# RedFly-Shield_v12.net
KiCad netlist of a schematic drawn in EAGLE
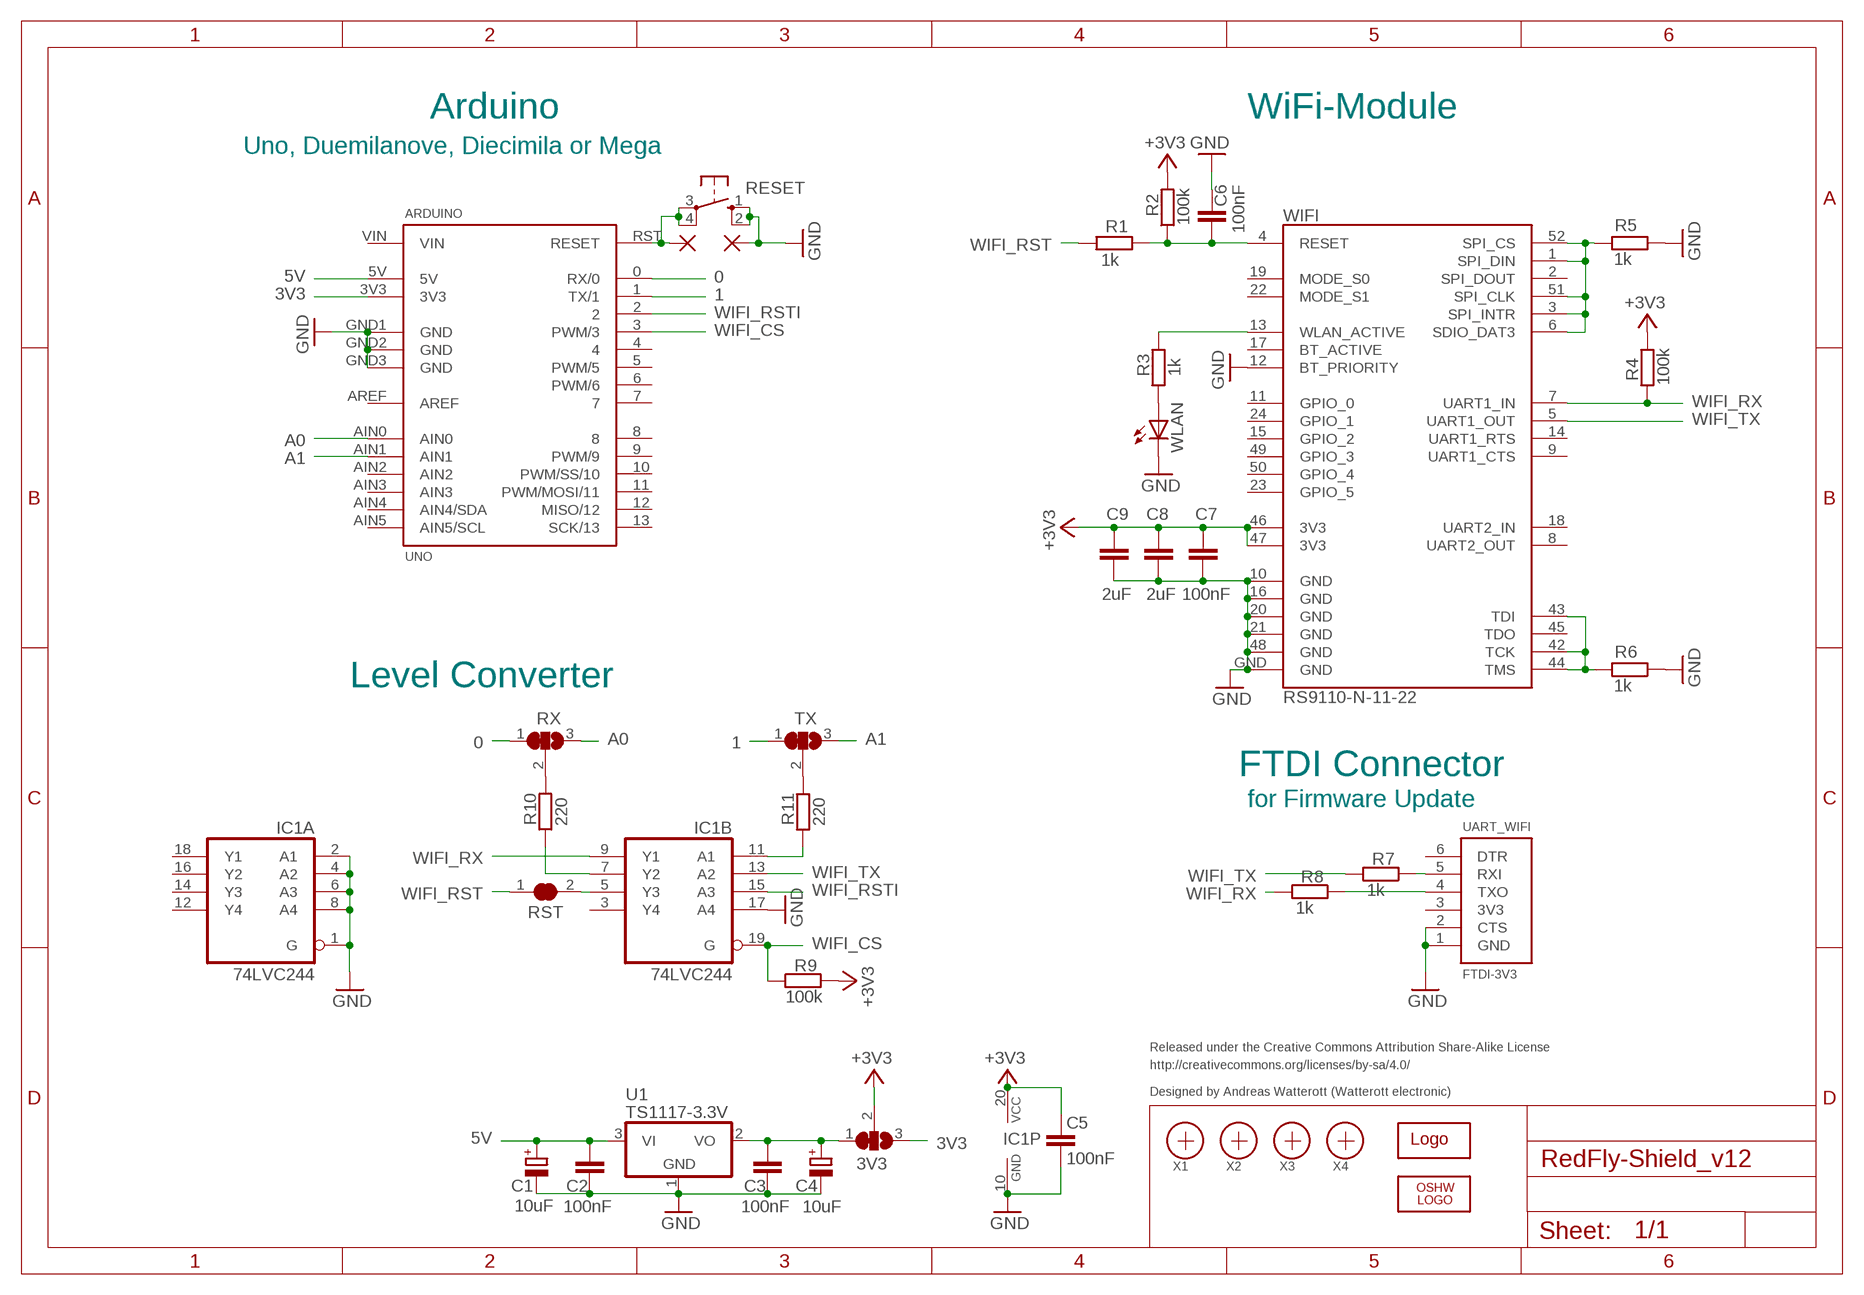
[diagram p0: schematic, sheet 1]

(export (version "E")
  (design (tool "Eeschema 10.0.6"))
  (components
    (comp (ref "3V3")
      (value "SJ2W")
      (footprint "eagle-import:SJ_2")
      (libsource (lib "eagle-import") (part "SJ2W"))
    )
    (comp (ref "ARDUINO")
      (value "UNO")
      (footprint "eagle-import:DUEMILANOVE")
      (libsource (lib "eagle-import") (part "DUEMILANOVE"))
    )
    (comp (ref "C1")
      (value "10uF")
      (footprint "eagle-import:153CLV-0505")
      (libsource (lib "eagle-import") (part "CPOL-EU153CLV-0505"))
    )
    (comp (ref "C2")
      (value "100nF")
      (footprint "eagle-import:C0603")
      (libsource (lib "eagle-import") (part "C-EUC0603"))
    )
    (comp (ref "C3")
      (value "100nF")
      (footprint "eagle-import:C0603")
      (libsource (lib "eagle-import") (part "C-EUC0603"))
    )
    (comp (ref "C4")
      (value "10uF")
      (footprint "eagle-import:153CLV-0505")
      (libsource (lib "eagle-import") (part "CPOL-EU153CLV-0505"))
    )
    (comp (ref "C5")
      (value "100nF")
      (footprint "eagle-import:C0603")
      (libsource (lib "eagle-import") (part "C-EUC0603"))
    )
    (comp (ref "C6")
      (value "100nF")
      (footprint "eagle-import:C0603")
      (libsource (lib "eagle-import") (part "C-EUC0603"))
    )
    (comp (ref "C7")
      (value "100nF")
      (footprint "eagle-import:C0603")
      (libsource (lib "eagle-import") (part "C-EUC0603"))
    )
    (comp (ref "C8")
      (value "2uF")
      (footprint "eagle-import:C0603")
      (libsource (lib "eagle-import") (part "C-EUC0603"))
    )
    (comp (ref "C9")
      (value "2uF")
      (footprint "eagle-import:C0603")
      (libsource (lib "eagle-import") (part "C-EUC0603"))
    )
    (comp (ref "GND")
      (value "SMD2")
      (footprint "eagle-import:SMD1,27-2,54")
      (libsource (lib "eagle-import") (part "SMD2"))
    )
    (comp (ref "IC1")
      (value "74LVC244")
      (footprint "eagle-import:SO20W")
      (libsource (lib "eagle-import") (part "74244DWHC"))
    )
    (comp (ref "LOGO1")
      (value "OSHW_LOGO_6MILX0100-NT")
      (footprint "eagle-import:OSHW_6X100_NOTEXT")
      (libsource (lib "eagle-import") (part "OSHW_LOGO_6MILX0100-NT"))
    )
    (comp (ref "R1")
      (value "1k")
      (footprint "eagle-import:R0603")
      (libsource (lib "eagle-import") (part "R-EU_R0603"))
    )
    (comp (ref "R2")
      (value "100k")
      (footprint "eagle-import:R0603")
      (libsource (lib "eagle-import") (part "R-EU_R0603"))
    )
    (comp (ref "R3")
      (value "1k")
      (footprint "eagle-import:R0603")
      (libsource (lib "eagle-import") (part "R-EU_R0603"))
    )
    (comp (ref "R4")
      (value "100k")
      (footprint "eagle-import:R0603")
      (libsource (lib "eagle-import") (part "R-EU_R0603"))
    )
    (comp (ref "R5")
      (value "1k")
      (footprint "eagle-import:R0603")
      (libsource (lib "eagle-import") (part "R-EU_R0603"))
    )
    (comp (ref "R6")
      (value "1k")
      (footprint "eagle-import:R0603")
      (libsource (lib "eagle-import") (part "R-EU_R0603"))
    )
    (comp (ref "R7")
      (value "1k")
      (footprint "eagle-import:R0603")
      (libsource (lib "eagle-import") (part "R-EU_R0603"))
    )
    (comp (ref "R8")
      (value "1k")
      (footprint "eagle-import:R0603")
      (libsource (lib "eagle-import") (part "R-EU_R0603"))
    )
    (comp (ref "R9")
      (value "100k")
      (footprint "eagle-import:R0603")
      (libsource (lib "eagle-import") (part "R-EU_R0603"))
    )
    (comp (ref "R10")
      (value "220")
      (footprint "eagle-import:R0603")
      (libsource (lib "eagle-import") (part "R-EU_R0603"))
    )
    (comp (ref "R11")
      (value "220")
      (footprint "eagle-import:R0603")
      (libsource (lib "eagle-import") (part "R-EU_R0603"))
    )
    (comp (ref "RESET")
      (value "10-XX")
      (footprint "eagle-import:B3F-10XX")
      (fields (field (name "MPN") "B3F-1000"))
      (libsource (lib "eagle-import") (part "10-XX"))
    )
    (comp (ref "RST") (value "SJ") (footprint "eagle-import:SJ") (libsource (lib "eagle-import") (part "SJ")))
    (comp (ref "RST2")
      (value "SMD2")
      (footprint "eagle-import:SMD1,27-2,54")
      (libsource (lib "eagle-import") (part "SMD2"))
    )
    (comp (ref "RX")
      (value "SJ2W")
      (footprint "eagle-import:SJ_2")
      (libsource (lib "eagle-import") (part "SJ2W"))
    )
    (comp (ref "TX")
      (value "SJ2W")
      (footprint "eagle-import:SJ_2")
      (libsource (lib "eagle-import") (part "SJ2W"))
    )
    (comp (ref "U$1")
      (value "WE-LOGO")
      (footprint "eagle-import:WE-LOGO")
      (libsource (lib "eagle-import") (part "WE-LOGO"))
    )
    (comp (ref "U1")
      (value "TS1117-3.3V")
      (footprint "eagle-import:SOT223")
      (libsource (lib "eagle-import") (part "TS1117"))
    )
    (comp (ref "UART_WIFI")
      (value "FTDI-3V3")
      (footprint "eagle-import:FTDI")
      (libsource (lib "eagle-import") (part "FTDI"))
    )
    (comp (ref "WIFI")
      (value "RS9110-N-11-22")
      (footprint "eagle-import:RS9110-N-11-21")
      (libsource (lib "eagle-import") (part "RS9110-N-11-21"))
    )
    (comp (ref "WLAN")
      (value "LEDCHIPLED_0603")
      (footprint "eagle-import:CHIPLED_0603")
      (libsource (lib "eagle-import") (part "LEDCHIPLED_0603"))
    )
    (comp (ref "X1")
      (value "PASSER")
      (footprint "eagle-import:PASSER")
      (libsource (lib "eagle-import") (part "PASSER"))
    )
    (comp (ref "X2")
      (value "PASSER")
      (footprint "eagle-import:PASSER")
      (libsource (lib "eagle-import") (part "PASSER"))
    )
    (comp (ref "X3")
      (value "PASSER")
      (footprint "eagle-import:PASSER")
      (libsource (lib "eagle-import") (part "PASSER"))
    )
    (comp (ref "X4")
      (value "PASSER")
      (footprint "eagle-import:PASSER")
      (libsource (lib "eagle-import") (part "PASSER"))
    )
  )
  (nets
    (net (code "1") (name "+3V3") (class "Default")
      (node (ref "3V3") (pin "2") (pinfunction "2_2") (pintype "passive"))
      (node (ref "C5") (pin "1") (pinfunction "1_1") (pintype "passive"))
      (node (ref "C7") (pin "1") (pinfunction "1_1") (pintype "passive"))
      (node (ref "C8") (pin "1") (pinfunction "1_1") (pintype "passive"))
      (node (ref "C9") (pin "1") (pinfunction "1_1") (pintype "passive"))
      (node (ref "IC1") (pin "20") (pinfunction "VCC_20") (pintype "power_in"))
      (node (ref "R2") (pin "2") (pinfunction "2_2") (pintype "passive"))
      (node (ref "R4") (pin "1") (pinfunction "1_1") (pintype "passive"))
      (node (ref "R9") (pin "2") (pinfunction "2_2") (pintype "passive"))
      (node (ref "WIFI") (pin "46") (pinfunction "3V3_46") (pintype "power_in"))
      (node (ref "WIFI") (pin "47") (pinfunction "3V3_47") (pintype "power_in"))
    )
    (net (code "2") (name "/0") (class "Default")
      (node (ref "ARDUINO") (pin "0") (pinfunction "RX/0_0") (pintype "bidirectional"))
      (node (ref "RX") (pin "1") (pinfunction "1_1") (pintype "passive"))
    )
    (net (code "3") (name "/1") (class "Default")
      (node (ref "ARDUINO") (pin "1") (pinfunction "TX/1_1") (pintype "bidirectional"))
      (node (ref "TX") (pin "1") (pinfunction "1_1") (pintype "passive"))
    )
    (net (code "4") (name "/3V3") (class "Default")
      (node (ref "3V3") (pin "3") (pinfunction "3_3") (pintype "passive"))
      (node (ref "ARDUINO") (pin "3V3") (pinfunction "3V3_3V3") (pintype "power_in"))
    )
    (net (code "5") (name "/5V") (class "Default")
      (node (ref "ARDUINO") (pin "5V") (pinfunction "5V_5V") (pintype "power_in"))
      (node (ref "C1") (pin "+") (pinfunction "+_+") (pintype "passive"))
      (node (ref "C2") (pin "1") (pinfunction "1_1") (pintype "passive"))
      (node (ref "U1") (pin "3") (pinfunction "VI_3") (pintype "input"))
    )
    (net (code "6") (name "/A0") (class "Default")
      (node (ref "ARDUINO") (pin "AIN0") (pinfunction "AIN0_AIN0") (pintype "bidirectional"))
      (node (ref "RX") (pin "3") (pinfunction "3_3") (pintype "passive"))
    )
    (net (code "7") (name "/A1") (class "Default")
      (node (ref "ARDUINO") (pin "AIN1") (pinfunction "AIN1_AIN1") (pintype "bidirectional"))
      (node (ref "TX") (pin "3") (pinfunction "3_3") (pintype "passive"))
    )
    (net (code "8") (name "/AREF") (class "Default")
      (node (ref "ARDUINO") (pin "AREF") (pinfunction "AREF_AREF") (pintype "power_in"))
    )
    (net (code "9") (name "/VIN") (class "Default")
      (node (ref "ARDUINO") (pin "VIN") (pinfunction "VIN_VIN") (pintype "power_in"))
    )
    (net (code "10") (name "/WIFI_CS") (class "Default")
      (node (ref "ARDUINO") (pin "3") (pinfunction "PWM/3_3") (pintype "bidirectional"))
      (node (ref "IC1") (pin "19") (pinfunction "G_19") (pintype "input"))
      (node (ref "R9") (pin "1") (pinfunction "1_1") (pintype "passive"))
    )
    (net (code "11") (name "/WIFI_RST") (class "Default")
      (node (ref "R1") (pin "2") (pinfunction "2_2") (pintype "passive"))
      (node (ref "RST") (pin "1") (pinfunction "1_1") (pintype "passive"))
    )
    (net (code "12") (name "/WIFI_RSTI") (class "Default")
      (node (ref "ARDUINO") (pin "2") (pinfunction "2_2") (pintype "bidirectional"))
      (node (ref "IC1") (pin "15") (pinfunction "A3_15") (pintype "input"))
    )
    (net (code "13") (name "/WIFI_RX") (class "Default")
      (node (ref "IC1") (pin "9") (pinfunction "Y1_9") (pintype "tri_state"))
      (node (ref "R4") (pin "2") (pinfunction "2_2") (pintype "passive"))
      (node (ref "R8") (pin "2") (pinfunction "2_2") (pintype "passive"))
      (node (ref "WIFI") (pin "7") (pinfunction "UART1_IN_7") (pintype "bidirectional"))
    )
    (net (code "14") (name "/WIFI_TX") (class "Default")
      (node (ref "IC1") (pin "13") (pinfunction "A2_13") (pintype "input"))
      (node (ref "R7") (pin "2") (pinfunction "2_2") (pintype "passive"))
      (node (ref "WIFI") (pin "5") (pinfunction "UART1_OUT_5") (pintype "bidirectional"))
    )
    (net (code "15") (name "GND") (class "Default")
      (node (ref "ARDUINO") (pin "GND1") (pinfunction "GND_GND1") (pintype "power_in"))
      (node (ref "ARDUINO") (pin "GND2") (pinfunction "GND_GND2") (pintype "power_in"))
      (node (ref "ARDUINO") (pin "GND3") (pinfunction "GND_GND3") (pintype "power_in"))
      (node (ref "C1") (pin "-") (pinfunction "-_-") (pintype "passive"))
      (node (ref "C2") (pin "2") (pinfunction "2_2") (pintype "passive"))
      (node (ref "C3") (pin "2") (pinfunction "2_2") (pintype "passive"))
      (node (ref "C4") (pin "-") (pinfunction "-_-") (pintype "passive"))
      (node (ref "C5") (pin "2") (pinfunction "2_2") (pintype "passive"))
      (node (ref "C6") (pin "1") (pinfunction "1_1") (pintype "passive"))
      (node (ref "C7") (pin "2") (pinfunction "2_2") (pintype "passive"))
      (node (ref "C8") (pin "2") (pinfunction "2_2") (pintype "passive"))
      (node (ref "C9") (pin "2") (pinfunction "2_2") (pintype "passive"))
      (node (ref "GND") (pin "1") (pinfunction "P_1") (pintype "passive"))
      (node (ref "IC1") (pin "1") (pinfunction "G_1") (pintype "input"))
      (node (ref "IC1") (pin "10") (pinfunction "GND_10") (pintype "power_in"))
      (node (ref "IC1") (pin "17") (pinfunction "A4_17") (pintype "input"))
      (node (ref "IC1") (pin "2") (pinfunction "A1_2") (pintype "input"))
      (node (ref "IC1") (pin "4") (pinfunction "A2_4") (pintype "input"))
      (node (ref "IC1") (pin "6") (pinfunction "A3_6") (pintype "input"))
      (node (ref "IC1") (pin "8") (pinfunction "A4_8") (pintype "input"))
      (node (ref "R5") (pin "1") (pinfunction "1_1") (pintype "passive"))
      (node (ref "R6") (pin "1") (pinfunction "1_1") (pintype "passive"))
      (node (ref "RESET") (pin "1") (pinfunction "S_1") (pintype "passive"))
      (node (ref "RESET") (pin "2") (pinfunction "S1_2") (pintype "passive"))
      (node (ref "U1") (pin "1") (pinfunction "GND_1") (pintype "passive"))
      (node (ref "UART_WIFI") (pin "1") (pinfunction "GND_1") (pintype "bidirectional"))
      (node (ref "UART_WIFI") (pin "2") (pinfunction "CTS_2") (pintype "bidirectional"))
      (node (ref "WIFI") (pin "10") (pinfunction "GND_10") (pintype "power_in"))
      (node (ref "WIFI") (pin "12") (pinfunction "BT_PRIORITY_12") (pintype "bidirectional"))
      (node (ref "WIFI") (pin "16") (pinfunction "GND_16") (pintype "power_in"))
      (node (ref "WIFI") (pin "20") (pinfunction "GND_20") (pintype "power_in"))
      (node (ref "WIFI") (pin "21") (pinfunction "GND_21") (pintype "power_in"))
      (node (ref "WIFI") (pin "48") (pinfunction "GND_48") (pintype "power_in"))
      (node (ref "WIFI") (pin "GND") (pinfunction "GND_GND") (pintype "power_in"))
      (node (ref "WLAN") (pin "C") (pinfunction "C_C") (pintype "passive"))
    )
    (net (code "16") (name "Net-(ARDUINO-RESET)") (class "Default")
      (node (ref "ARDUINO") (pin "RST") (pinfunction "RESET_RST") (pintype "bidirectional"))
      (node (ref "RESET") (pin "3") (pinfunction "P_3") (pintype "passive"))
      (node (ref "RESET") (pin "4") (pinfunction "P1_4") (pintype "passive"))
      (node (ref "RST2") (pin "1") (pinfunction "P_1") (pintype "passive"))
    )
    (net (code "17") (name "Net-(IC1B-A1)") (class "Default")
      (node (ref "IC1") (pin "11") (pinfunction "A1_11") (pintype "input"))
      (node (ref "R11") (pin "2") (pinfunction "2_2") (pintype "passive"))
    )
    (net (code "18") (name "Net-(IC1B-Y2)") (class "Default")
      (node (ref "IC1") (pin "7") (pinfunction "Y2_7") (pintype "tri_state"))
      (node (ref "R10") (pin "1") (pinfunction "1_1") (pintype "passive"))
    )
    (net (code "19") (name "Net-(IC1B-Y3)") (class "Default")
      (node (ref "IC1") (pin "5") (pinfunction "Y3_5") (pintype "tri_state"))
      (node (ref "RST") (pin "2") (pinfunction "2_2") (pintype "passive"))
    )
    (net (code "20") (name "Net-(R3-Pad2)") (class "Default")
      (node (ref "R3") (pin "2") (pinfunction "2_2") (pintype "passive"))
      (node (ref "WLAN") (pin "A") (pinfunction "A_A") (pintype "passive"))
    )
    (net (code "21") (name "Net-(R10-Pad2)") (class "Default")
      (node (ref "R10") (pin "2") (pinfunction "2_2") (pintype "passive"))
      (node (ref "RX") (pin "2") (pinfunction "2_2") (pintype "passive"))
    )
    (net (code "22") (name "Net-(R11-Pad1)") (class "Default")
      (node (ref "R11") (pin "1") (pinfunction "1_1") (pintype "passive"))
      (node (ref "TX") (pin "2") (pinfunction "2_2") (pintype "passive"))
    )
    (net (code "23") (name "Net-(U1-VO)") (class "Default")
      (node (ref "3V3") (pin "1") (pinfunction "1_1") (pintype "passive"))
      (node (ref "C3") (pin "1") (pinfunction "1_1") (pintype "passive"))
      (node (ref "C4") (pin "+") (pinfunction "+_+") (pintype "passive"))
      (node (ref "U1") (pin "2") (pinfunction "VO_2") (pintype "passive"))
    )
    (net (code "24") (name "Net-(UART_WIFI-RXI)") (class "Default")
      (node (ref "R7") (pin "1") (pinfunction "1_1") (pintype "passive"))
      (node (ref "UART_WIFI") (pin "5") (pinfunction "RXI_5") (pintype "bidirectional"))
    )
    (net (code "25") (name "Net-(UART_WIFI-TXO)") (class "Default")
      (node (ref "R8") (pin "1") (pinfunction "1_1") (pintype "passive"))
      (node (ref "UART_WIFI") (pin "4") (pinfunction "TXO_4") (pintype "bidirectional"))
    )
    (net (code "26") (name "Net-(WIFI-RESET)") (class "Default")
      (node (ref "C6") (pin "2") (pinfunction "2_2") (pintype "passive"))
      (node (ref "R1") (pin "1") (pinfunction "1_1") (pintype "passive"))
      (node (ref "R2") (pin "1") (pinfunction "1_1") (pintype "passive"))
      (node (ref "WIFI") (pin "4") (pinfunction "RESET_4") (pintype "bidirectional"))
    )
    (net (code "27") (name "Net-(WIFI-SDIO_DAT3)") (class "Default")
      (node (ref "R5") (pin "2") (pinfunction "2_2") (pintype "passive"))
      (node (ref "WIFI") (pin "1") (pinfunction "SPI_DIN_1") (pintype "bidirectional"))
      (node (ref "WIFI") (pin "3") (pinfunction "SPI_INTR_3") (pintype "bidirectional"))
      (node (ref "WIFI") (pin "51") (pinfunction "SPI_CLK_51") (pintype "bidirectional"))
      (node (ref "WIFI") (pin "52") (pinfunction "SPI_CS_52") (pintype "bidirectional"))
      (node (ref "WIFI") (pin "6") (pinfunction "SDIO_DAT3_6") (pintype "bidirectional"))
    )
    (net (code "28") (name "Net-(WIFI-TCK)") (class "Default")
      (node (ref "R6") (pin "2") (pinfunction "2_2") (pintype "passive"))
      (node (ref "WIFI") (pin "42") (pinfunction "TCK_42") (pintype "bidirectional"))
      (node (ref "WIFI") (pin "43") (pinfunction "TDI_43") (pintype "bidirectional"))
      (node (ref "WIFI") (pin "44") (pinfunction "TMS_44") (pintype "bidirectional"))
    )
    (net (code "29") (name "Net-(WIFI-WLAN_ACTIVE)") (class "Default")
      (node (ref "R3") (pin "1") (pinfunction "1_1") (pintype "passive"))
      (node (ref "WIFI") (pin "13") (pinfunction "WLAN_ACTIVE_13") (pintype "bidirectional"))
    )
    (net (code "30") (name "unconnected-(ARDUINO-AIN4{slash}SDA-PadAIN4)") (class "Default")
      (node (ref "ARDUINO") (pin "AIN4") (pinfunction "AIN4/SDA_AIN4") (pintype "bidirectional"))
    )
    (net (code "31") (name "unconnected-(ARDUINO-AIN5{slash}SCL-PadAIN5)") (class "Default")
      (node (ref "ARDUINO") (pin "AIN5") (pinfunction "AIN5/SCL_AIN5") (pintype "bidirectional"))
    )
    (net (code "32") (name "unconnected-(ARDUINO-MISO{slash}12-Pad12)") (class "Default")
      (node (ref "ARDUINO") (pin "12") (pinfunction "MISO/12_12") (pintype "bidirectional"))
    )
    (net (code "33") (name "unconnected-(ARDUINO-PWM{slash}5-Pad5)") (class "Default")
      (node (ref "ARDUINO") (pin "5") (pinfunction "PWM/5_5") (pintype "bidirectional"))
    )
    (net (code "34") (name "unconnected-(ARDUINO-PWM{slash}6-Pad6)") (class "Default")
      (node (ref "ARDUINO") (pin "6") (pinfunction "PWM/6_6") (pintype "bidirectional"))
    )
    (net (code "35") (name "unconnected-(ARDUINO-PWM{slash}9-Pad9)") (class "Default")
      (node (ref "ARDUINO") (pin "9") (pinfunction "PWM/9_9") (pintype "bidirectional"))
    )
    (net (code "36") (name "unconnected-(ARDUINO-PWM{slash}MOSI{slash}11-Pad11)") (class "Default")
      (node (ref "ARDUINO") (pin "11") (pinfunction "PWM/MOSI/11_11") (pintype "bidirectional"))
    )
    (net (code "37") (name "unconnected-(ARDUINO-PWM{slash}SS{slash}10-Pad10)") (class "Default")
      (node (ref "ARDUINO") (pin "10") (pinfunction "PWM/SS/10_10") (pintype "bidirectional"))
    )
    (net (code "38") (name "unconnected-(ARDUINO-Pad4)") (class "Default")
      (node (ref "ARDUINO") (pin "4") (pinfunction "4_4") (pintype "bidirectional"))
    )
    (net (code "39") (name "unconnected-(ARDUINO-Pad7)") (class "Default")
      (node (ref "ARDUINO") (pin "7") (pinfunction "7_7") (pintype "bidirectional"))
    )
    (net (code "40") (name "unconnected-(ARDUINO-Pad8)") (class "Default")
      (node (ref "ARDUINO") (pin "8") (pinfunction "8_8") (pintype "bidirectional"))
    )
    (net (code "41") (name "unconnected-(ARDUINO-PadAIN2)") (class "Default")
      (node (ref "ARDUINO") (pin "AIN2") (pinfunction "AIN2_AIN2") (pintype "bidirectional"))
    )
    (net (code "42") (name "unconnected-(ARDUINO-PadAIN3)") (class "Default")
      (node (ref "ARDUINO") (pin "AIN3") (pinfunction "AIN3_AIN3") (pintype "bidirectional"))
    )
    (net (code "43") (name "unconnected-(ARDUINO-SCK{slash}13-Pad13)") (class "Default")
      (node (ref "ARDUINO") (pin "13") (pinfunction "SCK/13_13") (pintype "bidirectional"))
    )
    (net (code "44") (name "unconnected-(IC1A-Y1-Pad18)") (class "Default")
      (node (ref "IC1") (pin "18") (pinfunction "Y1_18") (pintype "tri_state"))
    )
    (net (code "45") (name "unconnected-(IC1A-Y2-Pad16)") (class "Default")
      (node (ref "IC1") (pin "16") (pinfunction "Y2_16") (pintype "tri_state"))
    )
    (net (code "46") (name "unconnected-(IC1A-Y3-Pad14)") (class "Default")
      (node (ref "IC1") (pin "14") (pinfunction "Y3_14") (pintype "tri_state"))
    )
    (net (code "47") (name "unconnected-(IC1A-Y4-Pad12)") (class "Default")
      (node (ref "IC1") (pin "12") (pinfunction "Y4_12") (pintype "tri_state"))
    )
    (net (code "48") (name "unconnected-(IC1B-Y4-Pad3)") (class "Default")
      (node (ref "IC1") (pin "3") (pinfunction "Y4_3") (pintype "tri_state"))
    )
    (net (code "49") (name "unconnected-(UART_WIFI-3V3-Pad3)") (class "Default")
      (node (ref "UART_WIFI") (pin "3") (pinfunction "3V3_3") (pintype "bidirectional"))
    )
    (net (code "50") (name "unconnected-(UART_WIFI-DTR-Pad6)") (class "Default")
      (node (ref "UART_WIFI") (pin "6") (pinfunction "DTR_6") (pintype "bidirectional"))
    )
    (net (code "51") (name "unconnected-(WIFI-BT_ACTIVE-Pad17)") (class "Default")
      (node (ref "WIFI") (pin "17") (pinfunction "BT_ACTIVE_17") (pintype "bidirectional"))
    )
    (net (code "52") (name "unconnected-(WIFI-GPIO_0-Pad11)") (class "Default")
      (node (ref "WIFI") (pin "11") (pinfunction "GPIO_0_11") (pintype "bidirectional"))
    )
    (net (code "53") (name "unconnected-(WIFI-GPIO_1-Pad24)") (class "Default")
      (node (ref "WIFI") (pin "24") (pinfunction "GPIO_1_24") (pintype "bidirectional"))
    )
    (net (code "54") (name "unconnected-(WIFI-GPIO_2-Pad15)") (class "Default")
      (node (ref "WIFI") (pin "15") (pinfunction "GPIO_2_15") (pintype "bidirectional"))
    )
    (net (code "55") (name "unconnected-(WIFI-GPIO_3-Pad49)") (class "Default")
      (node (ref "WIFI") (pin "49") (pinfunction "GPIO_3_49") (pintype "bidirectional"))
    )
    (net (code "56") (name "unconnected-(WIFI-GPIO_4-Pad50)") (class "Default")
      (node (ref "WIFI") (pin "50") (pinfunction "GPIO_4_50") (pintype "bidirectional"))
    )
    (net (code "57") (name "unconnected-(WIFI-GPIO_5-Pad23)") (class "Default")
      (node (ref "WIFI") (pin "23") (pinfunction "GPIO_5_23") (pintype "bidirectional"))
    )
    (net (code "58") (name "unconnected-(WIFI-MODE_S0-Pad19)") (class "Default")
      (node (ref "WIFI") (pin "19") (pinfunction "MODE_S0_19") (pintype "bidirectional"))
    )
    (net (code "59") (name "unconnected-(WIFI-MODE_S1-Pad22)") (class "Default")
      (node (ref "WIFI") (pin "22") (pinfunction "MODE_S1_22") (pintype "bidirectional"))
    )
    (net (code "60") (name "unconnected-(WIFI-SPI_DOUT-Pad2)") (class "Default")
      (node (ref "WIFI") (pin "2") (pinfunction "SPI_DOUT_2") (pintype "bidirectional"))
    )
    (net (code "61") (name "unconnected-(WIFI-TDO-Pad45)") (class "Default")
      (node (ref "WIFI") (pin "45") (pinfunction "TDO_45") (pintype "bidirectional"))
    )
    (net (code "62") (name "unconnected-(WIFI-UART1_CTS-Pad9)") (class "Default")
      (node (ref "WIFI") (pin "9") (pinfunction "UART1_CTS_9") (pintype "bidirectional"))
    )
    (net (code "63") (name "unconnected-(WIFI-UART1_RTS-Pad14)") (class "Default")
      (node (ref "WIFI") (pin "14") (pinfunction "UART1_RTS_14") (pintype "bidirectional"))
    )
    (net (code "64") (name "unconnected-(WIFI-UART2_IN-Pad18)") (class "Default")
      (node (ref "WIFI") (pin "18") (pinfunction "UART2_IN_18") (pintype "bidirectional"))
    )
    (net (code "65") (name "unconnected-(WIFI-UART2_OUT-Pad8)") (class "Default")
      (node (ref "WIFI") (pin "8") (pinfunction "UART2_OUT_8") (pintype "bidirectional"))
    )
  )
)
